# tweeq-Stamp_IMU_6DOF_v4.net
KiCad netlist of a schematic drawn in EAGLE
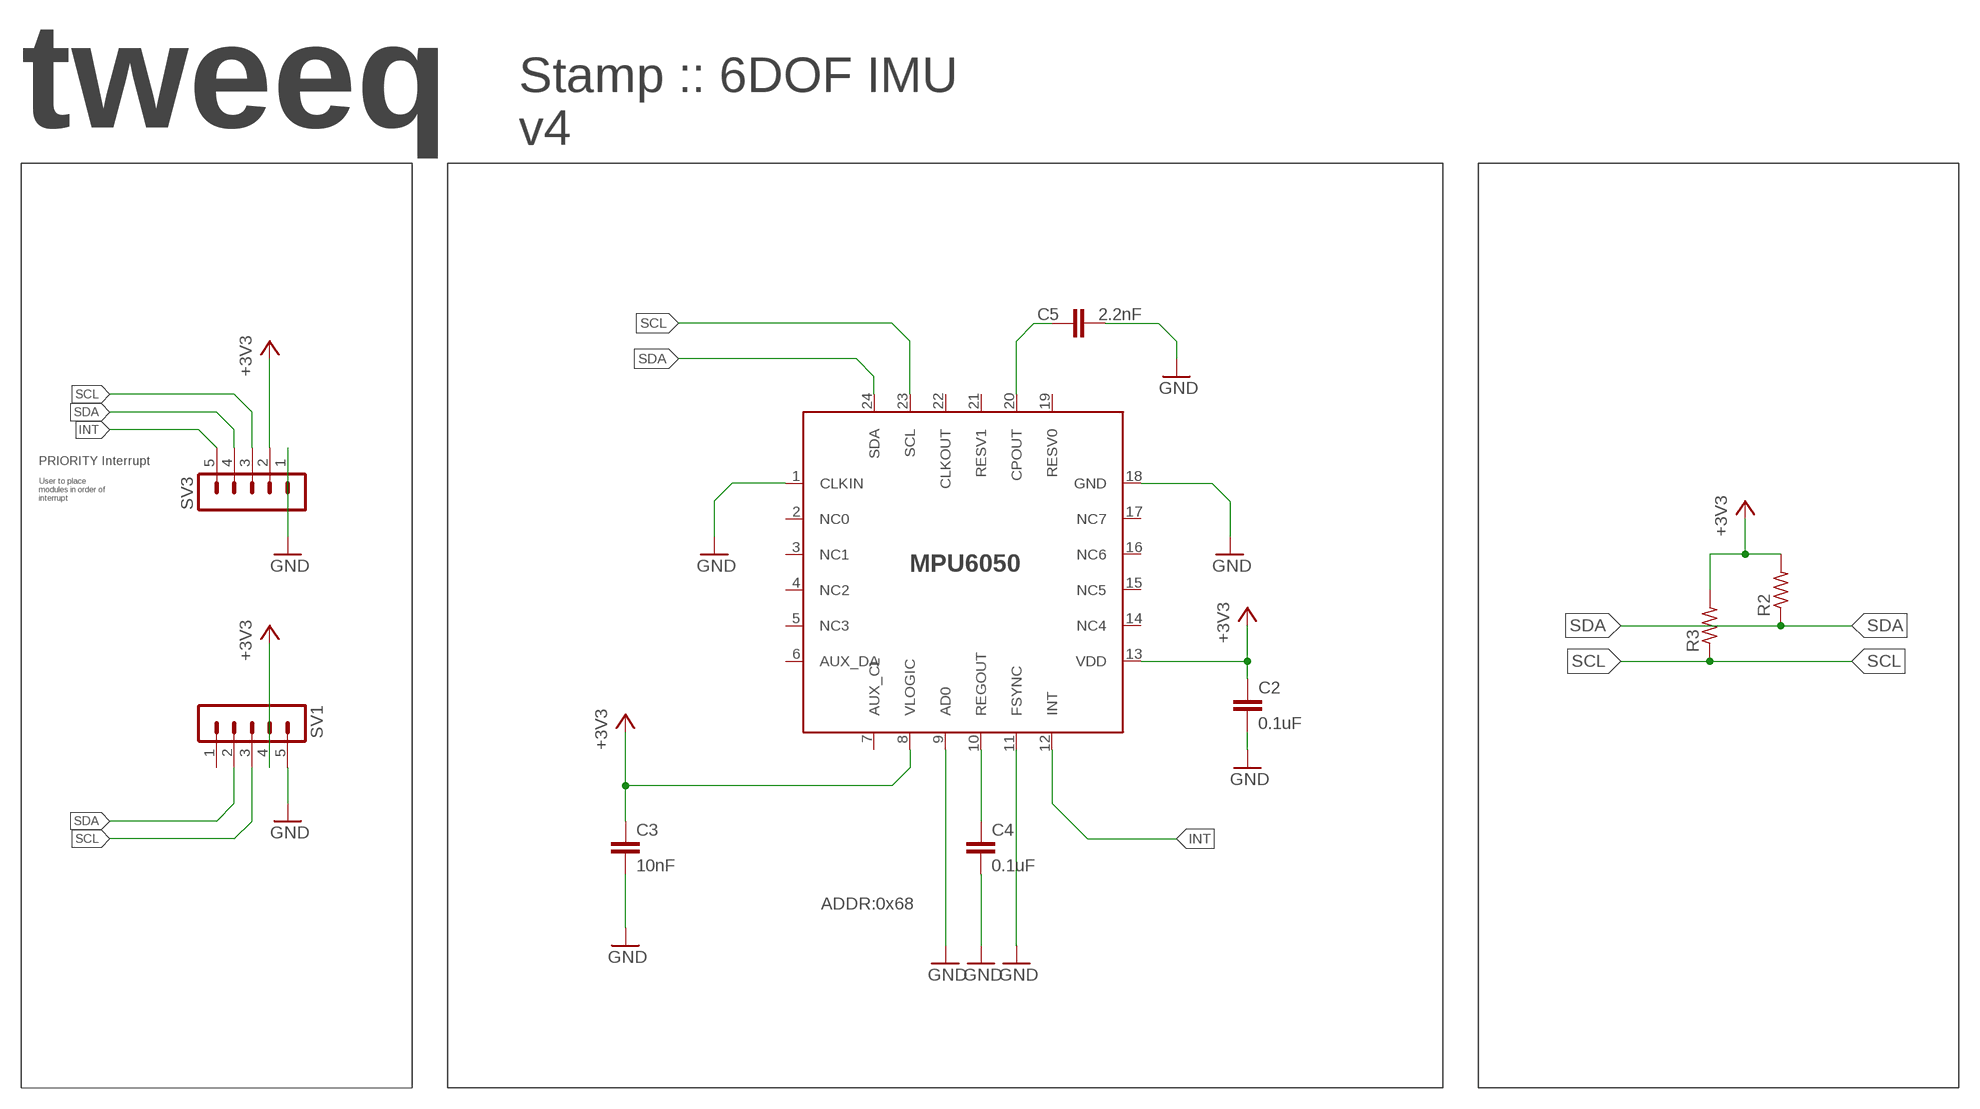
[diagram p0: schematic, sheet 1]

(export (version "E")
  (design (tool "Eeschema 10.0.6"))
  (components
    (comp (ref "C2")
      (value "0.1uF")
      (footprint "eagle-import:C0603K")
      (libsource (lib "eagle-import") (part "C-EUC0603K"))
    )
    (comp (ref "C3")
      (value "10nF")
      (footprint "eagle-import:C0603K")
      (libsource (lib "eagle-import") (part "C-EUC0603K"))
    )
    (comp (ref "C4")
      (value "0.1uF")
      (footprint "eagle-import:C0603K")
      (libsource (lib "eagle-import") (part "C-EUC0603K"))
    )
    (comp (ref "C5")
      (value "2.2nF")
      (footprint "eagle-import:C0603K")
      (libsource (lib "eagle-import") (part "C-EUC0603K"))
    )
    (comp (ref "R2")
      (value "R-US_R0603")
      (footprint "eagle-import:R0603")
      (libsource (lib "eagle-import") (part "R-US_R0603"))
    )
    (comp (ref "R3")
      (value "R-US_R0603")
      (footprint "eagle-import:R0603")
      (libsource (lib "eagle-import") (part "R-US_R0603"))
    )
    (comp (ref "SV1")
      (value "M05-1STAMP")
      (footprint "eagle-import:1X05-1.5MM-STAMP")
      (libsource (lib "eagle-import") (part "M05-1STAMP"))
    )
    (comp (ref "SV3")
      (value "M05-1STAMP")
      (footprint "eagle-import:1X05-1.5MM-STAMP")
      (libsource (lib "eagle-import") (part "M05-1STAMP"))
    )
    (comp (ref "U1")
      (value "MPU6050")
      (footprint "eagle-import:QFN24")
      (libsource (lib "eagle-import") (part "MPU6050"))
    )
  )
  (nets
    (net (code "1") (name "+3V3") (class "Default")
      (node (ref "C2") (pin "1") (pinfunction "1_1") (pintype "passive"))
      (node (ref "C3") (pin "1") (pinfunction "1_1") (pintype "passive"))
      (node (ref "R2") (pin "2") (pinfunction "2_2") (pintype "passive"))
      (node (ref "R3") (pin "2") (pinfunction "2_2") (pintype "passive"))
      (node (ref "SV1") (pin "4") (pinfunction "4_4") (pintype "passive"))
      (node (ref "SV3") (pin "2") (pinfunction "2_2") (pintype "passive"))
      (node (ref "U1") (pin "13") (pinfunction "VDD_13") (pintype "bidirectional"))
      (node (ref "U1") (pin "8") (pinfunction "VLOGIC_8") (pintype "bidirectional"))
    )
    (net (code "2") (name "GND") (class "Default")
      (node (ref "C2") (pin "2") (pinfunction "2_2") (pintype "passive"))
      (node (ref "C3") (pin "2") (pinfunction "2_2") (pintype "passive"))
      (node (ref "C4") (pin "2") (pinfunction "2_2") (pintype "passive"))
      (node (ref "C5") (pin "2") (pinfunction "2_2") (pintype "passive"))
      (node (ref "SV1") (pin "5") (pinfunction "5_5") (pintype "passive"))
      (node (ref "SV3") (pin "1") (pinfunction "1_1") (pintype "passive"))
      (node (ref "U1") (pin "1") (pinfunction "CLKIN_1") (pintype "bidirectional"))
      (node (ref "U1") (pin "11") (pinfunction "FSYNC_11") (pintype "bidirectional"))
      (node (ref "U1") (pin "18") (pinfunction "GND_18") (pintype "bidirectional"))
      (node (ref "U1") (pin "9") (pinfunction "AD0_9") (pintype "bidirectional"))
    )
    (net (code "3") (name "INT") (class "Default")
      (node (ref "SV3") (pin "5") (pinfunction "5_5") (pintype "passive"))
      (node (ref "U1") (pin "12") (pinfunction "INT_12") (pintype "bidirectional"))
    )
    (net (code "4") (name "Net-(U1-CPOUT)") (class "Default")
      (node (ref "C5") (pin "1") (pinfunction "1_1") (pintype "passive"))
      (node (ref "U1") (pin "20") (pinfunction "CPOUT_20") (pintype "bidirectional"))
    )
    (net (code "5") (name "Net-(U1-REGOUT)") (class "Default")
      (node (ref "C4") (pin "1") (pinfunction "1_1") (pintype "passive"))
      (node (ref "U1") (pin "10") (pinfunction "REGOUT_10") (pintype "bidirectional"))
    )
    (net (code "6") (name "SCL") (class "Default")
      (node (ref "R3") (pin "1") (pinfunction "1_1") (pintype "passive"))
      (node (ref "SV1") (pin "3") (pinfunction "3_3") (pintype "passive"))
      (node (ref "SV3") (pin "3") (pinfunction "3_3") (pintype "passive"))
      (node (ref "U1") (pin "23") (pinfunction "SCL_23") (pintype "bidirectional"))
    )
    (net (code "7") (name "SDA") (class "Default")
      (node (ref "R2") (pin "1") (pinfunction "1_1") (pintype "passive"))
      (node (ref "SV1") (pin "2") (pinfunction "2_2") (pintype "passive"))
      (node (ref "SV3") (pin "4") (pinfunction "4_4") (pintype "passive"))
      (node (ref "U1") (pin "24") (pinfunction "SDA_24") (pintype "bidirectional"))
    )
    (net (code "8") (name "unconnected-(SV1-Pad1)") (class "Default")
      (node (ref "SV1") (pin "1") (pinfunction "1_1") (pintype "passive"))
    )
    (net (code "9") (name "unconnected-(U1-AUX_CL-Pad7)") (class "Default")
      (node (ref "U1") (pin "7") (pinfunction "AUX_CL_7") (pintype "bidirectional"))
    )
    (net (code "10") (name "unconnected-(U1-AUX_DA-Pad6)") (class "Default")
      (node (ref "U1") (pin "6") (pinfunction "AUX_DA_6") (pintype "bidirectional"))
    )
    (net (code "11") (name "unconnected-(U1-CLKOUT-Pad22)") (class "Default")
      (node (ref "U1") (pin "22") (pinfunction "CLKOUT_22") (pintype "bidirectional"))
    )
    (net (code "12") (name "unconnected-(U1-NC0-Pad2)") (class "Default")
      (node (ref "U1") (pin "2") (pinfunction "NC0_2") (pintype "no_connect"))
    )
    (net (code "13") (name "unconnected-(U1-NC1-Pad3)") (class "Default")
      (node (ref "U1") (pin "3") (pinfunction "NC1_3") (pintype "no_connect"))
    )
    (net (code "14") (name "unconnected-(U1-NC2-Pad4)") (class "Default")
      (node (ref "U1") (pin "4") (pinfunction "NC2_4") (pintype "no_connect"))
    )
    (net (code "15") (name "unconnected-(U1-NC3-Pad5)") (class "Default")
      (node (ref "U1") (pin "5") (pinfunction "NC3_5") (pintype "no_connect"))
    )
    (net (code "16") (name "unconnected-(U1-NC4-Pad14)") (class "Default")
      (node (ref "U1") (pin "14") (pinfunction "NC4_14") (pintype "no_connect"))
    )
    (net (code "17") (name "unconnected-(U1-NC5-Pad15)") (class "Default")
      (node (ref "U1") (pin "15") (pinfunction "NC5_15") (pintype "no_connect"))
    )
    (net (code "18") (name "unconnected-(U1-NC6-Pad16)") (class "Default")
      (node (ref "U1") (pin "16") (pinfunction "NC6_16") (pintype "no_connect"))
    )
    (net (code "19") (name "unconnected-(U1-NC7-Pad17)") (class "Default")
      (node (ref "U1") (pin "17") (pinfunction "NC7_17") (pintype "no_connect"))
    )
    (net (code "20") (name "unconnected-(U1-RESV0-Pad19)") (class "Default")
      (node (ref "U1") (pin "19") (pinfunction "RESV0_19") (pintype "bidirectional"))
    )
    (net (code "21") (name "unconnected-(U1-RESV1-Pad21)") (class "Default")
      (node (ref "U1") (pin "21") (pinfunction "RESV1_21") (pintype "bidirectional"))
    )
  )
)
